# Circuit.net
KiCad netlist of a schematic drawn in Altium Designer
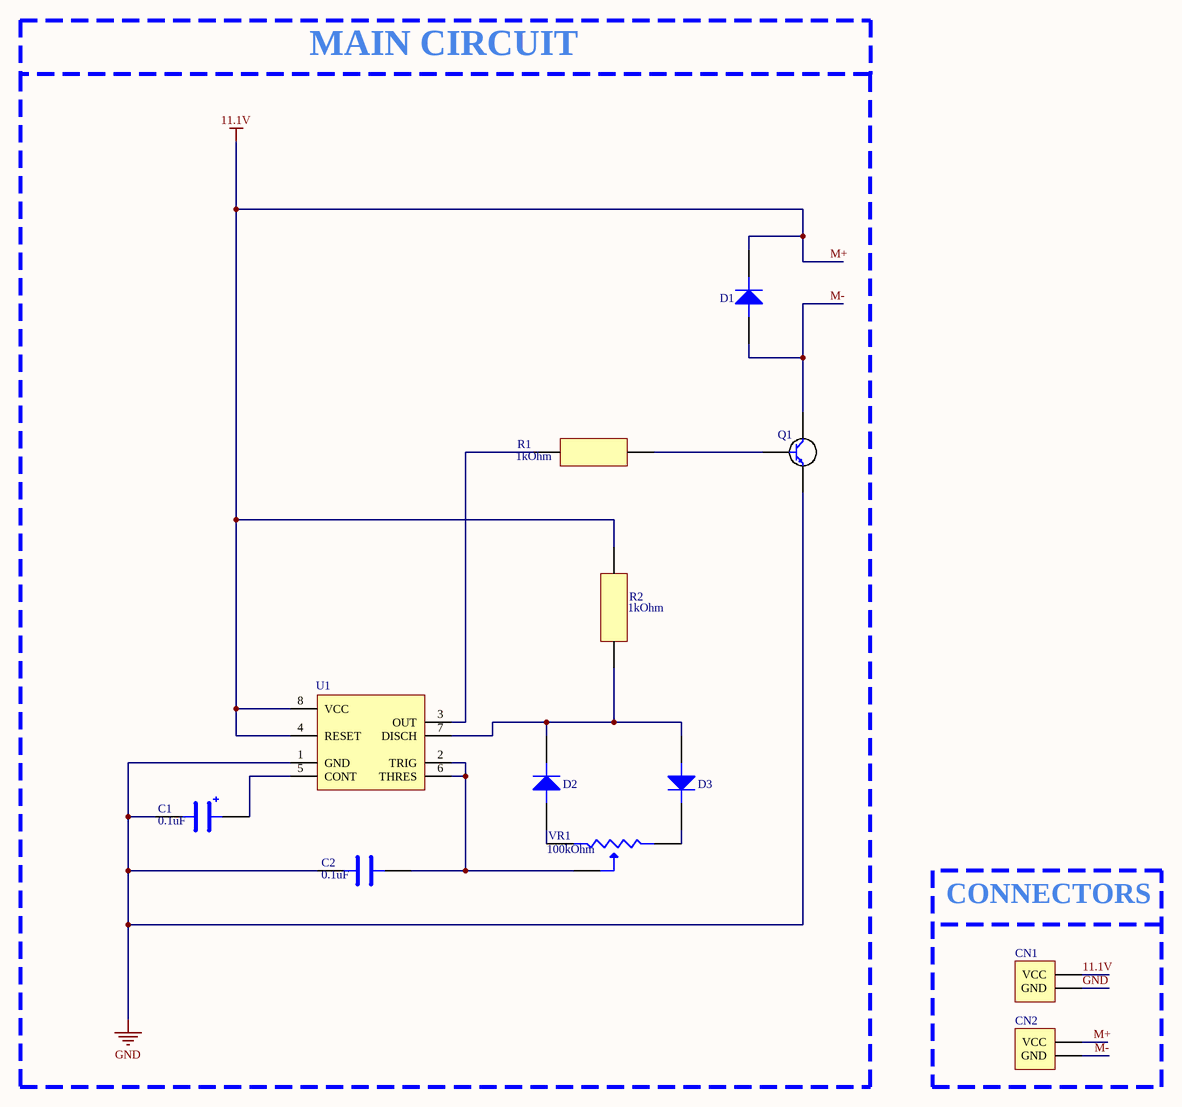
[diagram p0: Circuit.SchDoc]

(export (version "E")
  (design (tool "Eeschema 10.0.6"))
  (components
    (comp (ref "C1")
      (value "860020772001")
      (footprint "CAP_ALUM")
      (description "WCAP-ATG5 Aluminum Electrolytic Capacitors")
      (fields
        (field (name "MANUFACTURER") "Wurth Electronics")
        (field (name "CAPACITOR") "0.1uF")
        (field (name "DESIGNED BY") "Nasıf Can Peltek")
      )
      (libsource (lib "N555_Library") (part "CAP ALUM 0.1uF"))
    )
    (comp (ref "C2")
      (value "R82EC3100DQ70J")
      (footprint "CAP_FILM")
      (description "Cap Film 0.1uF 100V PET 5% (7.2 X 2.5 X 6.5mm) Radial 5mm 105C Ammo Pack")
      (fields
        (field (name "MANUFACTURER") "KEMET")
        (field (name "CAPACITOR") "0.1uF")
        (field (name "DESIGNED BY") "Nasıf Can Peltek")
      )
      (libsource (lib "N555_Library") (part "CAP FILM 0.1uF"))
    )
    (comp (ref "CN1")
      (value "732-10955-ND")
      (footprint "BULK")
      (description "Series 1377 - 5.00 mm Horizontal Entry with Pressure Clamp WR-TBL, 2 pin")
      (fields
        (field (name "MANUFACTURER") "Wurth Electronics")
        (field (name "MANUFACTURER PART NUMBER") "691137710002")
        (field (name "DESIGNED BY") "Nasıf Can Peltek")
      )
      (libsource (lib "N555_Library") (part "TERMINAL BLOCK"))
    )
    (comp (ref "CN2")
      (value "732-10955-ND")
      (footprint "BULK")
      (description "Series 1377 - 5.00 mm Horizontal Entry with Pressure Clamp WR-TBL, 2 pin")
      (fields
        (field (name "MANUFACTURER") "Wurth Electronics")
        (field (name "MANUFACTURER PART NUMBER") "691137710002")
        (field (name "DESIGNED BY") "Nasıf Can Peltek")
      )
      (libsource (lib "N555_Library") (part "TERMINAL BLOCK"))
    )
    (comp (ref "D1")
      (value "1N4007G-T")
      (footprint "DO41")
      (description "Diode Standard 1000V (1kV) 1A Through Hole DO-41")
      (fields (field (name "MANUFACTURER") "Diodes") (field (name "DESIGNED BY") "Nasıf Can Peltek"))
      (libsource (lib "N555_Library") (part "DIODE 1N4007"))
    )
    (comp (ref "D2")
      (value "1N4007G-T")
      (footprint "DO41")
      (description "Diode Standard 1000V (1kV) 1A Through Hole DO-41")
      (fields (field (name "MANUFACTURER") "Diodes") (field (name "DESIGNED BY") "Nasıf Can Peltek"))
      (libsource (lib "N555_Library") (part "DIODE 1N4007"))
    )
    (comp (ref "D3")
      (value "1N4007G-T")
      (footprint "DO41")
      (description "Diode Standard 1000V (1kV) 1A Through Hole DO-41")
      (fields (field (name "MANUFACTURER") "Diodes") (field (name "DESIGNED BY") "Nasıf Can Peltek"))
      (libsource (lib "N555_Library") (part "DIODE 1N4007"))
    )
    (comp (ref "Q1")
      (value "497-2543-5-ND")
      (footprint "TO220")
      (description "TIP122 Series NPN/PNP 100 V 5 A Complimentary Darlington Transistor - TO-220-3")
      (fields
        (field (name "MANUFACTURER") "STMicroelectronics")
        (field (name "MANUFACTURER PART NUMBER") "TIP122")
        (field (name "DESIGNED BY") "Nasıf Can Peltek")
      )
      (libsource (lib "N555_Library") (part "BJT DARLINGTON"))
    )
    (comp (ref "R1")
      (value "CF14JT1K00")
      (footprint "AXIAL")
      (description "Res Carbon Film 1K Ohm 5% 1/4W -400ppm/°C to 0ppm/°C Conformal AXL Thru-Hole T/R")
      (fields
        (field (name "MANUFACTURER") "Stackpole Electronics")
        (field (name "POWER") "1/4W")
        (field (name "RESISTOR") "1kOhm")
        (field (name "DESIGNED BY") "Nasıf Can Peltek")
      )
      (libsource (lib "N555_Library") (part "RES 1K OHM"))
    )
    (comp (ref "R2")
      (value "CF14JT1K00")
      (footprint "AXIAL")
      (description "Res Carbon Film 1K Ohm 5% 1/4W -400ppm/°C to 0ppm/°C Conformal AXL Thru-Hole T/R")
      (fields
        (field (name "MANUFACTURER") "Stackpole Electronics")
        (field (name "POWER") "1/4W")
        (field (name "RESISTOR") "1kOhm")
        (field (name "DESIGNED BY") "Nasıf Can Peltek")
      )
      (libsource (lib "") (part "RES 1K OHM_1"))
    )
    (comp (ref "U1")
      (value "NE555P")
      (footprint "DIP8")
      (description "555 Type, Timer/Oscillator (Single) Through Hole 8-PDIP")
      (fields
        (field (name "MANUFACTURER") "Texas Instruments")
        (field (name "DESIGNED BY") "Nasıf Can Peltek")
      )
      (libsource (lib "N555_Library") (part "NE555"))
    )
    (comp (ref "VR1")
      (value "P160KN2-0EC15B100K")
      (footprint "POT")
      (description "P160 Series 0.2 W 100 kO Side Adjust Long PC Pins Conductive Plastic Potentiometer")
      (fields
        (field (name "MANUFACTURER") "TT BI")
        (field (name "RESISTOR") "100kOhm")
        (field (name "DESIGNED BY") "Nasıf Can Peltek")
      )
      (libsource (lib "N555_Library") (part "POT 100K OHM"))
    )
  )
  (nets
    (net (code "1") (name "/M-") (class "Default")
      (node (ref "CN2") (pin "2") (pinfunction "GND_2") (pintype "passive"))
      (node (ref "D1") (pin "1") (pinfunction "1_1") (pintype "passive"))
      (node (ref "Q1") (pin "2") (pinfunction "Collector_2") (pintype "passive"))
    )
    (net (code "2") (name "11.1V") (class "Default")
      (node (ref "CN1") (pin "1") (pinfunction "VCC_1") (pintype "passive"))
      (node (ref "CN2") (pin "1") (pinfunction "VCC_1") (pintype "passive"))
      (node (ref "D1") (pin "2") (pinfunction "2_2") (pintype "passive"))
      (node (ref "R2") (pin "2") (pinfunction "2_2") (pintype "passive"))
      (node (ref "U1") (pin "4") (pinfunction "RESET_4") (pintype "passive"))
      (node (ref "U1") (pin "8") (pinfunction "VCC_8") (pintype "passive"))
    )
    (net (code "3") (name "GND") (class "Default")
      (node (ref "C1") (pin "1") (pinfunction "Cathode_1") (pintype "passive"))
      (node (ref "C2") (pin "1") (pinfunction "1_1") (pintype "passive"))
      (node (ref "CN1") (pin "2") (pinfunction "GND_2") (pintype "passive"))
      (node (ref "Q1") (pin "3") (pinfunction "Emitter_3") (pintype "passive"))
      (node (ref "U1") (pin "1") (pinfunction "GND_1") (pintype "passive"))
    )
    (net (code "4") (name "Net-(C1-Anode)") (class "Default")
      (node (ref "C1") (pin "2") (pinfunction "Anode_2") (pintype "passive"))
      (node (ref "U1") (pin "5") (pinfunction "CONT_5") (pintype "passive"))
    )
    (net (code "5") (name "Net-(D2-Pad1)") (class "Default")
      (node (ref "D2") (pin "1") (pinfunction "1_1") (pintype "passive"))
      (node (ref "VR1") (pin "1") (pinfunction "1_1") (pintype "passive"))
    )
    (net (code "6") (name "Net-(D3-Pad2)") (class "Default")
      (node (ref "D3") (pin "2") (pinfunction "2_2") (pintype "passive"))
      (node (ref "VR1") (pin "3") (pinfunction "3_3") (pintype "passive"))
    )
    (net (code "7") (name "Net-(Q1-Base)") (class "Default")
      (node (ref "Q1") (pin "1") (pinfunction "Base_1") (pintype "passive"))
      (node (ref "R1") (pin "2") (pinfunction "2_2") (pintype "passive"))
    )
    (net (code "8") (name "Net-(U1-DISCH)") (class "Default")
      (node (ref "D2") (pin "2") (pinfunction "2_2") (pintype "passive"))
      (node (ref "D3") (pin "1") (pinfunction "1_1") (pintype "passive"))
      (node (ref "R2") (pin "1") (pinfunction "1_1") (pintype "passive"))
      (node (ref "U1") (pin "7") (pinfunction "DISCH_7") (pintype "passive"))
    )
    (net (code "9") (name "Net-(U1-OUT)") (class "Default")
      (node (ref "R1") (pin "1") (pinfunction "1_1") (pintype "passive"))
      (node (ref "U1") (pin "3") (pinfunction "OUT_3") (pintype "passive"))
    )
    (net (code "10") (name "Net-(U1-THRES)") (class "Default")
      (node (ref "C2") (pin "2") (pinfunction "2_2") (pintype "passive"))
      (node (ref "U1") (pin "2") (pinfunction "TRIG_2") (pintype "passive"))
      (node (ref "U1") (pin "6") (pinfunction "THRES_6") (pintype "passive"))
      (node (ref "VR1") (pin "2") (pinfunction "2_2") (pintype "passive"))
    )
  )
)
